# blinker_earring.net
KiCad netlist of a schematic drawn in EAGLE
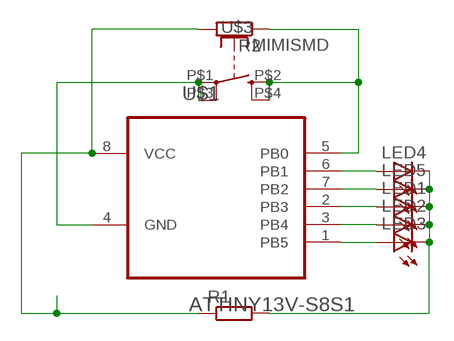
[diagram p0: schematic, sheet 1]

(export (version "E")
  (design (tool "Eeschema 10.0.6"))
  (components
    (comp (ref "LED1")
      (value "LEDSML1206")
      (footprint "eagle-import:SML1206")
      (libsource (lib "eagle-import") (part "LEDSML1206"))
    )
    (comp (ref "LED2")
      (value "LEDSML1206")
      (footprint "eagle-import:SML1206")
      (libsource (lib "eagle-import") (part "LEDSML1206"))
    )
    (comp (ref "LED3")
      (value "LEDSML1206")
      (footprint "eagle-import:SML1206")
      (libsource (lib "eagle-import") (part "LEDSML1206"))
    )
    (comp (ref "LED4")
      (value "LEDSML1206")
      (footprint "eagle-import:SML1206")
      (libsource (lib "eagle-import") (part "LEDSML1206"))
    )
    (comp (ref "LED5")
      (value "LEDSML1206")
      (footprint "eagle-import:SML1206")
      (libsource (lib "eagle-import") (part "LEDSML1206"))
    )
    (comp (ref "R1")
      (value "R-EU_R1206")
      (footprint "eagle-import:R1206")
      (libsource (lib "eagle-import") (part "R-EU_R1206"))
    )
    (comp (ref "R2")
      (value "R-EU_R1206")
      (footprint "eagle-import:R1206")
      (libsource (lib "eagle-import") (part "R-EU_R1206"))
    )
    (comp (ref "U$1")
      (value "ATTINY13V-S8S1")
      (footprint "eagle-import:ATTINY13A-SSU")
      (libsource (lib "eagle-import") (part "ATTINY13V-S8S1"))
    )
    (comp (ref "U$3")
      (value "MIMISMD")
      (footprint "eagle-import:MINISMD")
      (libsource (lib "eagle-import") (part "MIMISMD"))
    )
  )
  (nets
    (net (code "1") (name "Net-(LED1-PadC)") (class "Default")
      (node (ref "LED1") (pin "C") (pinfunction "C_C") (pintype "passive"))
      (node (ref "LED2") (pin "C") (pinfunction "C_C") (pintype "passive"))
      (node (ref "LED3") (pin "C") (pinfunction "C_C") (pintype "passive"))
      (node (ref "LED4") (pin "C") (pinfunction "C_C") (pintype "passive"))
      (node (ref "LED5") (pin "C") (pinfunction "C_C") (pintype "passive"))
      (node (ref "R1") (pin "2") (pinfunction "2_2") (pintype "passive"))
    )
    (net (code "2") (name "Net-(U$1-GND)") (class "Default")
      (node (ref "U$1") (pin "4") (pinfunction "GND_4") (pintype "passive"))
      (node (ref "U$3") (pin "P$1") (pinfunction "P_P$1") (pintype "passive"))
      (node (ref "U$3") (pin "P$3") (pinfunction "P_P$3") (pintype "passive"))
    )
    (net (code "3") (name "Net-(U$1-PB0)") (class "Default")
      (node (ref "R2") (pin "1") (pinfunction "1_1") (pintype "passive"))
      (node (ref "U$1") (pin "5") (pinfunction "PB0_5") (pintype "bidirectional"))
      (node (ref "U$3") (pin "P$2") (pinfunction "S_P$2") (pintype "passive"))
      (node (ref "U$3") (pin "P$4") (pinfunction "S_P$4") (pintype "passive"))
    )
    (net (code "4") (name "Net-(U$1-PB1)") (class "Default")
      (node (ref "LED4") (pin "A") (pinfunction "A_A") (pintype "passive"))
      (node (ref "U$1") (pin "6") (pinfunction "PB1_6") (pintype "bidirectional"))
    )
    (net (code "5") (name "Net-(U$1-PB2)") (class "Default")
      (node (ref "LED5") (pin "A") (pinfunction "A_A") (pintype "passive"))
      (node (ref "U$1") (pin "7") (pinfunction "PB2_7") (pintype "bidirectional"))
    )
    (net (code "6") (name "Net-(U$1-PB3)") (class "Default")
      (node (ref "LED1") (pin "A") (pinfunction "A_A") (pintype "passive"))
      (node (ref "U$1") (pin "2") (pinfunction "PB3_2") (pintype "bidirectional"))
    )
    (net (code "7") (name "Net-(U$1-PB4)") (class "Default")
      (node (ref "LED2") (pin "A") (pinfunction "A_A") (pintype "passive"))
      (node (ref "U$1") (pin "3") (pinfunction "PB4_3") (pintype "bidirectional"))
    )
    (net (code "8") (name "Net-(U$1-PB5)") (class "Default")
      (node (ref "LED3") (pin "A") (pinfunction "A_A") (pintype "passive"))
      (node (ref "U$1") (pin "1") (pinfunction "PB5_1") (pintype "bidirectional"))
    )
    (net (code "9") (name "Net-(U$1-VCC)") (class "Default")
      (node (ref "R1") (pin "1") (pinfunction "1_1") (pintype "passive"))
      (node (ref "R2") (pin "2") (pinfunction "2_2") (pintype "passive"))
      (node (ref "U$1") (pin "8") (pinfunction "VCC_8") (pintype "power_in"))
    )
  )
)
